# M_H_ext_rgb.net
KiCad netlist of a schematic drawn in EAGLE
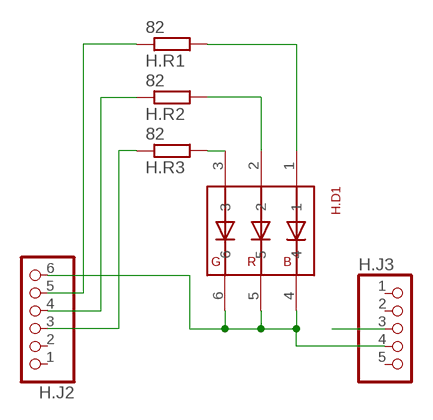
[diagram p0: schematic, sheet 1]

(export (version "E")
  (design (tool "Eeschema 10.0.6"))
  (components
    (comp (ref "H.D1")
      (value "RGB_WW-FCE50TC-Q1")
      (footprint "eagle-import:RGB_WW-FCE50TC-Q1")
      (libsource (lib "eagle-import") (part "RGB_WW-FCE50TC-Q1"))
    )
    (comp (ref "H.J2")
      (value "PINHD-1X6")
      (footprint "eagle-import:1X06")
      (libsource (lib "eagle-import") (part "PINHD-1X6"))
    )
    (comp (ref "H.J3")
      (value "PINHD-1X5")
      (footprint "eagle-import:1X05")
      (libsource (lib "eagle-import") (part "PINHD-1X5"))
    )
    (comp (ref "H.R1")
      (value "82")
      (footprint "eagle-import:R0603")
      (libsource (lib "eagle-import") (part "R-EU_R0603"))
    )
    (comp (ref "H.R2")
      (value "82")
      (footprint "eagle-import:R0603")
      (libsource (lib "eagle-import") (part "R-EU_R0603"))
    )
    (comp (ref "H.R3")
      (value "82")
      (footprint "eagle-import:R0603")
      (libsource (lib "eagle-import") (part "R-EU_R0603"))
    )
  )
  (nets
    (net (code "1") (name "Net-(H.D1-Pad1)") (class "Default")
      (node (ref "H.D1") (pin "1") (pinfunction "1_1") (pintype "bidirectional"))
      (node (ref "H.R1") (pin "2") (pinfunction "2_2") (pintype "passive"))
    )
    (net (code "2") (name "Net-(H.D1-Pad2)") (class "Default")
      (node (ref "H.D1") (pin "2") (pinfunction "2_2") (pintype "bidirectional"))
      (node (ref "H.R2") (pin "2") (pinfunction "2_2") (pintype "passive"))
    )
    (net (code "3") (name "Net-(H.D1-Pad3)") (class "Default")
      (node (ref "H.D1") (pin "3") (pinfunction "3_3") (pintype "bidirectional"))
      (node (ref "H.R3") (pin "2") (pinfunction "2_2") (pintype "passive"))
    )
    (net (code "4") (name "Net-(H.D1-Pad4)") (class "Default")
      (node (ref "H.D1") (pin "4") (pinfunction "4_4") (pintype "bidirectional"))
      (node (ref "H.D1") (pin "5") (pinfunction "5_5") (pintype "bidirectional"))
      (node (ref "H.D1") (pin "6") (pinfunction "6_6") (pintype "bidirectional"))
      (node (ref "H.J2") (pin "6") (pinfunction "6_6") (pintype "passive"))
      (node (ref "H.J3") (pin "4") (pinfunction "4_4") (pintype "passive"))
    )
    (net (code "5") (name "Net-(H.J2-Pad3)") (class "Default")
      (node (ref "H.J2") (pin "3") (pinfunction "3_3") (pintype "passive"))
      (node (ref "H.R3") (pin "1") (pinfunction "1_1") (pintype "passive"))
    )
    (net (code "6") (name "Net-(H.J2-Pad4)") (class "Default")
      (node (ref "H.J2") (pin "4") (pinfunction "4_4") (pintype "passive"))
      (node (ref "H.R2") (pin "1") (pinfunction "1_1") (pintype "passive"))
    )
    (net (code "7") (name "Net-(H.J2-Pad5)") (class "Default")
      (node (ref "H.J2") (pin "5") (pinfunction "5_5") (pintype "passive"))
      (node (ref "H.R1") (pin "1") (pinfunction "1_1") (pintype "passive"))
    )
    (net (code "8") (name "unconnected-(H.J2-Pad1)") (class "Default")
      (node (ref "H.J2") (pin "1") (pinfunction "1_1") (pintype "passive"))
    )
    (net (code "9") (name "unconnected-(H.J2-Pad2)") (class "Default")
      (node (ref "H.J2") (pin "2") (pinfunction "2_2") (pintype "passive"))
    )
    (net (code "10") (name "unconnected-(H.J3-Pad1)") (class "Default")
      (node (ref "H.J3") (pin "1") (pinfunction "1_1") (pintype "passive"))
    )
    (net (code "11") (name "unconnected-(H.J3-Pad2)") (class "Default")
      (node (ref "H.J3") (pin "2") (pinfunction "2_2") (pintype "passive"))
    )
    (net (code "12") (name "unconnected-(H.J3-Pad3)") (class "Default")
      (node (ref "H.J3") (pin "3") (pinfunction "3_3") (pintype "passive"))
    )
    (net (code "13") (name "unconnected-(H.J3-Pad5)") (class "Default")
      (node (ref "H.J3") (pin "5") (pinfunction "5_5") (pintype "passive"))
    )
  )
)
